# Pressure.net
KiCad netlist of a schematic drawn in EAGLE
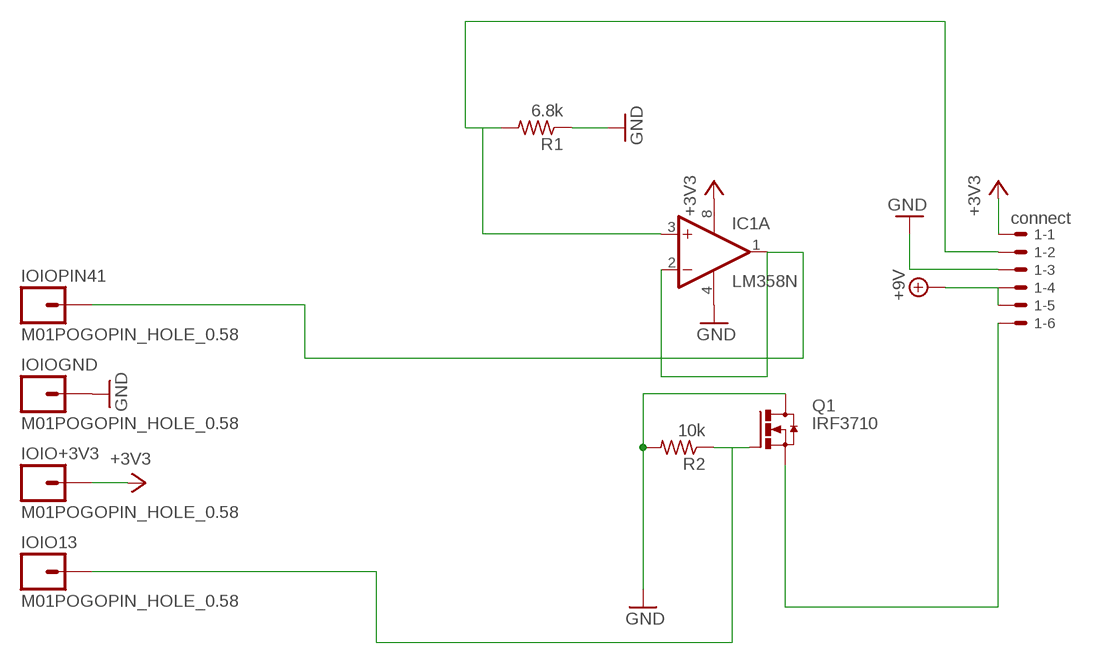
[diagram p0: schematic, sheet 1]

(export (version "E")
  (design (tool "Eeschema 10.0.6"))
  (components
    (comp (ref "1")
      (value "connect")
      (footprint "eagle-import:70543-06")
      (libsource (lib "eagle-import") (part "C-GRID-06-70543"))
    )
    (comp (ref "IC1")
      (value "LM358N")
      (footprint "eagle-import:DIL08")
      (libsource (lib "eagle-import") (part "LM358N"))
    )
    (comp (ref "IOIO+3V3")
      (value "M01POGOPIN_HOLE_0.58")
      (footprint "eagle-import:1X01_POGOPIN_HOLE_0.58")
      (libsource (lib "eagle-import") (part "M01POGOPIN_HOLE_0.58"))
    )
    (comp (ref "IOIO13")
      (value "M01POGOPIN_HOLE_0.58")
      (footprint "eagle-import:1X01_POGOPIN_HOLE_0.58")
      (libsource (lib "eagle-import") (part "M01POGOPIN_HOLE_0.58"))
    )
    (comp (ref "IOIOGND")
      (value "M01POGOPIN_HOLE_0.58")
      (footprint "eagle-import:1X01_POGOPIN_HOLE_0.58")
      (libsource (lib "eagle-import") (part "M01POGOPIN_HOLE_0.58"))
    )
    (comp (ref "IOIOPIN41")
      (value "M01POGOPIN_HOLE_0.58")
      (footprint "eagle-import:1X01_POGOPIN_HOLE_0.58")
      (libsource (lib "eagle-import") (part "M01POGOPIN_HOLE_0.58"))
    )
    (comp (ref "Q1")
      (value "IRF3710")
      (footprint "eagle-import:TO-220AB")
      (libsource (lib "eagle-import") (part "IRF3710"))
    )
    (comp (ref "R1")
      (value "6.8k")
      (footprint "eagle-import:0204_7")
      (libsource (lib "eagle-import") (part "R-US_0204/7"))
    )
    (comp (ref "R2")
      (value "10k")
      (footprint "eagle-import:0204_7")
      (libsource (lib "eagle-import") (part "R-US_0204/7"))
    )
  )
  (nets
    (net (code "1") (name "+3V3") (class "Default")
      (node (ref "1") (pin "1") (pinfunction "S_1") (pintype "passive"))
      (node (ref "IC1") (pin "8") (pinfunction "V+_8") (pintype "power_in"))
      (node (ref "IOIO+3V3") (pin "1") (pinfunction "1_1") (pintype "passive"))
    )
    (net (code "2") (name "+9V") (class "Default")
      (node (ref "1") (pin "4") (pinfunction "S_4") (pintype "passive"))
      (node (ref "1") (pin "5") (pinfunction "S_5") (pintype "passive"))
    )
    (net (code "3") (name "GND") (class "Default")
      (node (ref "1") (pin "3") (pinfunction "S_3") (pintype "passive"))
      (node (ref "IC1") (pin "4") (pinfunction "V-_4") (pintype "power_in"))
      (node (ref "IOIOGND") (pin "1") (pinfunction "1_1") (pintype "passive"))
      (node (ref "Q1") (pin "A2") (pinfunction "D_A2") (pintype "passive"))
      (node (ref "R1") (pin "1") (pinfunction "1_1") (pintype "passive"))
      (node (ref "R2") (pin "2") (pinfunction "2_2") (pintype "passive"))
    )
    (net (code "4") (name "Net-(1B-S)") (class "Default")
      (node (ref "1") (pin "2") (pinfunction "S_2") (pintype "passive"))
      (node (ref "IC1") (pin "3") (pinfunction "+IN_3") (pintype "input"))
      (node (ref "R1") (pin "2") (pinfunction "2_2") (pintype "passive"))
    )
    (net (code "5") (name "Net-(1F-S)") (class "Default")
      (node (ref "1") (pin "6") (pinfunction "S_6") (pintype "passive"))
      (node (ref "Q1") (pin "C") (pinfunction "S_C") (pintype "passive"))
    )
    (net (code "6") (name "Net-(IC1A--IN)") (class "Default")
      (node (ref "IC1") (pin "1") (pinfunction "OUT_1") (pintype "output"))
      (node (ref "IC1") (pin "2") (pinfunction "-IN_2") (pintype "input"))
      (node (ref "IOIOPIN41") (pin "1") (pinfunction "1_1") (pintype "passive"))
    )
    (net (code "7") (name "Net-(Q1-G)") (class "Default")
      (node (ref "IOIO13") (pin "1") (pinfunction "1_1") (pintype "passive"))
      (node (ref "Q1") (pin "A1") (pinfunction "G_A1") (pintype "passive"))
      (node (ref "R2") (pin "1") (pinfunction "1_1") (pintype "passive"))
    )
  )
)
